# esp8266_-_velky_stabilizator.net
KiCad netlist of a schematic drawn in EAGLE
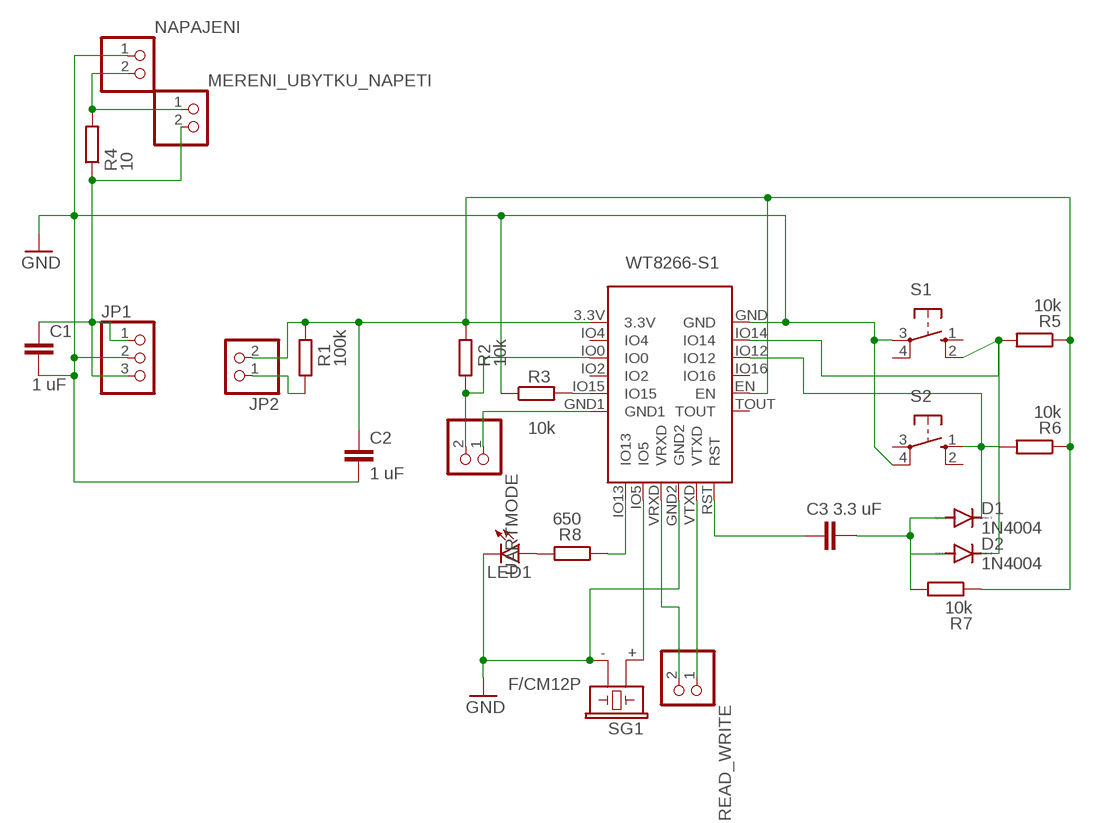
[diagram p0: schematic, sheet 1]

(export (version "E")
  (design (tool "Eeschema 10.0.6"))
  (components
    (comp (ref "C1")
      (value "1 uF")
      (footprint "eagle-import:C2.5-2")
      (libsource (lib "eagle-import") (part "C2.5/2"))
    )
    (comp (ref "C2")
      (value "1 uF")
      (footprint "eagle-import:C2.5-2")
      (libsource (lib "eagle-import") (part "C2.5/2"))
    )
    (comp (ref "C3")
      (value "3.3 uF")
      (footprint "eagle-import:C2.5-2")
      (libsource (lib "eagle-import") (part "C2.5/2"))
    )
    (comp (ref "D1")
      (value "1N4004")
      (footprint "eagle-import:DO41-10")
      (libsource (lib "eagle-import") (part "1N4004"))
    )
    (comp (ref "D2")
      (value "1N4004")
      (footprint "eagle-import:DO41-10")
      (libsource (lib "eagle-import") (part "1N4004"))
    )
    (comp (ref "JP1")
      (value "PINHD-1X3")
      (footprint "eagle-import:1X03")
      (libsource (lib "eagle-import") (part "PINHD-1X3"))
    )
    (comp (ref "JP2")
      (value "PINHD-1X2")
      (footprint "eagle-import:1X02")
      (libsource (lib "eagle-import") (part "PINHD-1X2"))
    )
    (comp (ref "LED1")
      (value "LED5MM")
      (footprint "eagle-import:LED5MM")
      (libsource (lib "eagle-import") (part "LED5MM"))
    )
    (comp (ref "MERENI_UBYTKU_NAPETI")
      (value "PINHD-1X2")
      (footprint "eagle-import:1X02")
      (libsource (lib "eagle-import") (part "PINHD-1X2"))
    )
    (comp (ref "NAPAJENI")
      (value "PINHD-1X2")
      (footprint "eagle-import:1X02")
      (libsource (lib "eagle-import") (part "PINHD-1X2"))
    )
    (comp (ref "R1")
      (value "100k")
      (footprint "eagle-import:0207_10")
      (libsource (lib "eagle-import") (part "R-EU_0207/10"))
    )
    (comp (ref "R2")
      (value "10k")
      (footprint "eagle-import:0207_10")
      (libsource (lib "eagle-import") (part "R-EU_0207/10"))
    )
    (comp (ref "R3")
      (value "10k")
      (footprint "eagle-import:0207_10")
      (libsource (lib "eagle-import") (part "R-EU_0207/10"))
    )
    (comp (ref "R4")
      (value "10")
      (footprint "eagle-import:0207_10")
      (libsource (lib "eagle-import") (part "R-EU_0207/10"))
    )
    (comp (ref "R5")
      (value "10k")
      (footprint "eagle-import:0207_10")
      (libsource (lib "eagle-import") (part "R-EU_0207/10"))
    )
    (comp (ref "R6")
      (value "10k")
      (footprint "eagle-import:0207_10")
      (libsource (lib "eagle-import") (part "R-EU_0207/10"))
    )
    (comp (ref "R7")
      (value "10k")
      (footprint "eagle-import:0207_10")
      (libsource (lib "eagle-import") (part "R-EU_0207/10"))
    )
    (comp (ref "R8")
      (value "650")
      (footprint "eagle-import:0207_10")
      (libsource (lib "eagle-import") (part "R-EU_0207/10"))
    )
    (comp (ref "READ_WRITE")
      (value "PINHD-1X2")
      (footprint "eagle-import:1X02")
      (libsource (lib "eagle-import") (part "PINHD-1X2"))
    )
    (comp (ref "S1")
      (value "10-XX")
      (footprint "eagle-import:B3F-10XX")
      (fields (field (name "MPN") "B3F-1000"))
      (libsource (lib "eagle-import") (part "10-XX"))
    )
    (comp (ref "S2")
      (value "10-XX")
      (footprint "eagle-import:B3F-10XX")
      (fields (field (name "MPN") "B3F-1000"))
      (libsource (lib "eagle-import") (part "10-XX"))
    )
    (comp (ref "SG1")
      (value "F/CM12P")
      (footprint "eagle-import:F_CM12P")
      (libsource (lib "eagle-import") (part "F/CM12P"))
    )
    (comp (ref "U$1")
      (value "WT8266-S1")
      (footprint "eagle-import:WT8266-S1")
      (libsource (lib "eagle-import") (part "WT8266-S1"))
    )
    (comp (ref "UARTMODE")
      (value "PINHD-1X2")
      (footprint "eagle-import:1X02")
      (libsource (lib "eagle-import") (part "PINHD-1X2"))
    )
  )
  (nets
    (net (code "1") (name "GND") (class "Default")
      (node (ref "C1") (pin "2") (pinfunction "2_2") (pintype "passive"))
      (node (ref "C2") (pin "2") (pinfunction "2_2") (pintype "passive"))
      (node (ref "JP1") (pin "2") (pinfunction "2_2") (pintype "passive"))
      (node (ref "LED1") (pin "K") (pinfunction "C_K") (pintype "passive"))
      (node (ref "NAPAJENI") (pin "1") (pinfunction "1_1") (pintype "passive"))
      (node (ref "R3") (pin "1") (pinfunction "1_1") (pintype "passive"))
      (node (ref "S1") (pin "3") (pinfunction "P_3") (pintype "passive"))
      (node (ref "S2") (pin "4") (pinfunction "P1_4") (pintype "passive"))
      (node (ref "SG1") (pin "-") (pinfunction "2_-") (pintype "passive"))
      (node (ref "U$1") (pin "GND") (pinfunction "GND_GND") (pintype "bidirectional"))
      (node (ref "U$1") (pin "GND2") (pinfunction "GND2_GND2") (pintype "bidirectional"))
    )
    (net (code "2") (name "Net-(C1-Pad1)") (class "Default")
      (node (ref "C1") (pin "1") (pinfunction "1_1") (pintype "passive"))
      (node (ref "JP1") (pin "1") (pinfunction "1_1") (pintype "passive"))
      (node (ref "JP1") (pin "3") (pinfunction "3_3") (pintype "passive"))
      (node (ref "MERENI_UBYTKU_NAPETI") (pin "2") (pinfunction "2_2") (pintype "passive"))
      (node (ref "R4") (pin "1") (pinfunction "1_1") (pintype "passive"))
    )
    (net (code "3") (name "Net-(C2-Pad1)") (class "Default")
      (node (ref "C2") (pin "1") (pinfunction "1_1") (pintype "passive"))
      (node (ref "JP2") (pin "2") (pinfunction "2_2") (pintype "passive"))
      (node (ref "R1") (pin "2") (pinfunction "2_2") (pintype "passive"))
      (node (ref "R2") (pin "2") (pinfunction "2_2") (pintype "passive"))
      (node (ref "R5") (pin "1") (pinfunction "1_1") (pintype "passive"))
      (node (ref "R6") (pin "1") (pinfunction "1_1") (pintype "passive"))
      (node (ref "R7") (pin "1") (pinfunction "1_1") (pintype "passive"))
      (node (ref "U$1") (pin "3.3V") (pinfunction "3.3V_3.3V") (pintype "bidirectional"))
      (node (ref "U$1") (pin "EN") (pinfunction "EN_EN") (pintype "bidirectional"))
    )
    (net (code "4") (name "Net-(C3-Pad1)") (class "Default")
      (node (ref "C3") (pin "1") (pinfunction "1_1") (pintype "passive"))
      (node (ref "U$1") (pin "RST") (pinfunction "RST_RST") (pintype "bidirectional"))
    )
    (net (code "5") (name "Net-(C3-Pad2)") (class "Default")
      (node (ref "C3") (pin "2") (pinfunction "2_2") (pintype "passive"))
      (node (ref "D1") (pin "A") (pinfunction "A_A") (pintype "passive"))
      (node (ref "D2") (pin "A") (pinfunction "A_A") (pintype "passive"))
      (node (ref "R7") (pin "2") (pinfunction "2_2") (pintype "passive"))
    )
    (net (code "6") (name "Net-(JP2-Pad1)") (class "Default")
      (node (ref "JP2") (pin "1") (pinfunction "1_1") (pintype "passive"))
      (node (ref "R1") (pin "1") (pinfunction "1_1") (pintype "passive"))
    )
    (net (code "7") (name "Net-(LED1-PadA)") (class "Default")
      (node (ref "LED1") (pin "A") (pinfunction "A_A") (pintype "passive"))
      (node (ref "R8") (pin "2") (pinfunction "2_2") (pintype "passive"))
    )
    (net (code "8") (name "Net-(MERENI_UBYTKU_NAPETI-Pad1)") (class "Default")
      (node (ref "MERENI_UBYTKU_NAPETI") (pin "1") (pinfunction "1_1") (pintype "passive"))
      (node (ref "NAPAJENI") (pin "2") (pinfunction "2_2") (pintype "passive"))
      (node (ref "R4") (pin "2") (pinfunction "2_2") (pintype "passive"))
    )
    (net (code "9") (name "Net-(R2-Pad1)") (class "Default")
      (node (ref "R2") (pin "1") (pinfunction "1_1") (pintype "passive"))
      (node (ref "U$1") (pin "IO0") (pinfunction "IO0_IO0") (pintype "bidirectional"))
      (node (ref "UARTMODE") (pin "2") (pinfunction "2_2") (pintype "passive"))
    )
    (net (code "10") (name "Net-(R3-Pad2)") (class "Default")
      (node (ref "R3") (pin "2") (pinfunction "2_2") (pintype "passive"))
      (node (ref "U$1") (pin "IO15") (pinfunction "IO15_IO15") (pintype "bidirectional"))
    )
    (net (code "11") (name "Net-(R8-Pad1)") (class "Default")
      (node (ref "R8") (pin "1") (pinfunction "1_1") (pintype "passive"))
      (node (ref "U$1") (pin "IO13") (pinfunction "IO13_IO13") (pintype "bidirectional"))
    )
    (net (code "12") (name "Net-(READ_WRITE-Pad1)") (class "Default")
      (node (ref "READ_WRITE") (pin "1") (pinfunction "1_1") (pintype "passive"))
      (node (ref "U$1") (pin "VTXD") (pinfunction "VTXD_VTXD") (pintype "bidirectional"))
    )
    (net (code "13") (name "Net-(READ_WRITE-Pad2)") (class "Default")
      (node (ref "READ_WRITE") (pin "2") (pinfunction "2_2") (pintype "passive"))
      (node (ref "U$1") (pin "VRXD") (pinfunction "VRXD_VRXD") (pintype "bidirectional"))
    )
    (net (code "14") (name "Net-(S1-S1)") (class "Default")
      (node (ref "D2") (pin "C") (pinfunction "C_C") (pintype "passive"))
      (node (ref "R5") (pin "2") (pinfunction "2_2") (pintype "passive"))
      (node (ref "S1") (pin "2") (pinfunction "S1_2") (pintype "passive"))
      (node (ref "U$1") (pin "IO14") (pinfunction "IO14_IO14") (pintype "bidirectional"))
    )
    (net (code "15") (name "Net-(S2-S)") (class "Default")
      (node (ref "D1") (pin "C") (pinfunction "C_C") (pintype "passive"))
      (node (ref "R6") (pin "2") (pinfunction "2_2") (pintype "passive"))
      (node (ref "S2") (pin "1") (pinfunction "S_1") (pintype "passive"))
      (node (ref "U$1") (pin "IO12") (pinfunction "IO12_IO12") (pintype "bidirectional"))
    )
    (net (code "16") (name "Net-(SG1-1)") (class "Default")
      (node (ref "SG1") (pin "+") (pinfunction "1_+") (pintype "passive"))
      (node (ref "U$1") (pin "IO5") (pinfunction "IO5_IO5") (pintype "bidirectional"))
    )
    (net (code "17") (name "Net-(U$1-PadGND1)") (class "Default")
      (node (ref "U$1") (pin "GND1") (pinfunction "GND1_GND1") (pintype "bidirectional"))
      (node (ref "UARTMODE") (pin "1") (pinfunction "1_1") (pintype "passive"))
    )
    (net (code "18") (name "unconnected-(S1-P1-Pad4)") (class "Default")
      (node (ref "S1") (pin "4") (pinfunction "P1_4") (pintype "passive"))
    )
    (net (code "19") (name "unconnected-(S1-S-Pad1)") (class "Default")
      (node (ref "S1") (pin "1") (pinfunction "S_1") (pintype "passive"))
    )
    (net (code "20") (name "unconnected-(S2-P-Pad3)") (class "Default")
      (node (ref "S2") (pin "3") (pinfunction "P_3") (pintype "passive"))
    )
    (net (code "21") (name "unconnected-(S2-S1-Pad2)") (class "Default")
      (node (ref "S2") (pin "2") (pinfunction "S1_2") (pintype "passive"))
    )
    (net (code "22") (name "unconnected-(U$1-PadIO2)") (class "Default")
      (node (ref "U$1") (pin "IO2") (pinfunction "IO2_IO2") (pintype "bidirectional"))
    )
    (net (code "23") (name "unconnected-(U$1-PadIO4)") (class "Default")
      (node (ref "U$1") (pin "IO4") (pinfunction "IO4_IO4") (pintype "bidirectional"))
    )
    (net (code "24") (name "unconnected-(U$1-PadIO16)") (class "Default")
      (node (ref "U$1") (pin "IO16") (pinfunction "IO16_IO16") (pintype "bidirectional"))
    )
    (net (code "25") (name "unconnected-(U$1-PadTOUT)") (class "Default")
      (node (ref "U$1") (pin "TOUT") (pinfunction "TOUT_TOUT") (pintype "bidirectional"))
    )
  )
)
